# aafilter.net
KiCad netlist of a schematic drawn in Altium Designer
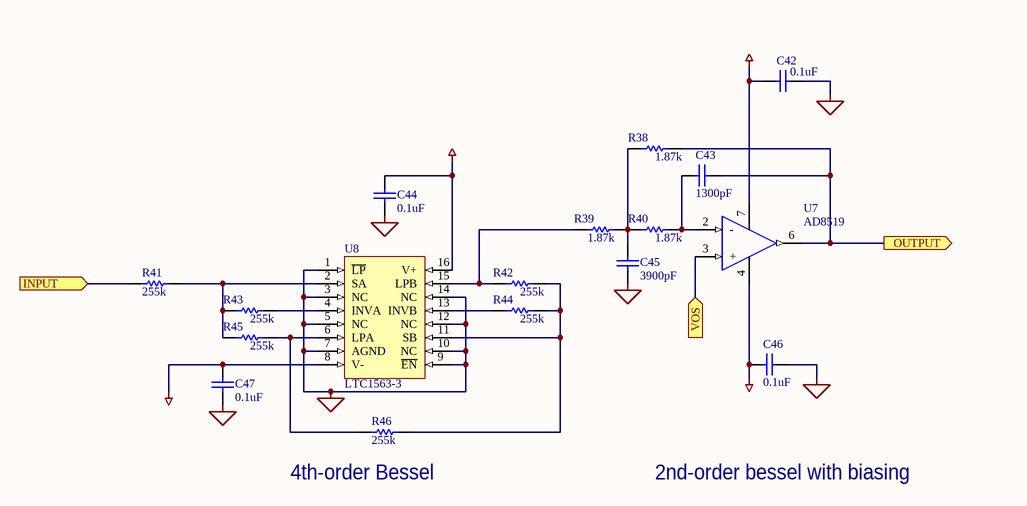
[diagram p0: aafilter.SCHDOC]

(export (version "E")
  (design (tool "Eeschema 10.0.6"))
  (components
    (comp (ref "C42")
      (value "Cap")
      (footprint "CC1608-0603")
      (description "Capacitor")
      (fields
        (field (name "MANUFACTURER") "Generic Components")
        (field (name "ALTIUM_VALUE") "0.1uF")
        (field (name "PUBLISHER") "Altium Limited")
      )
      (libsource (lib "Miscellaneous Devices") (part "Cap"))
    )
    (comp (ref "C43")
      (value "Cap")
      (footprint "CC1608-0603")
      (description "Capacitor")
      (fields
        (field (name "MANUFACTURER") "Generic Components")
        (field (name "ALTIUM_VALUE") "1300pF")
        (field (name "PUBLISHER") "Altium Limited")
      )
      (libsource (lib "Miscellaneous Devices") (part "Cap"))
    )
    (comp (ref "C44")
      (value "Cap")
      (footprint "CC1608-0603")
      (description "Capacitor")
      (fields
        (field (name "MANUFACTURER") "Generic Components")
        (field (name "ALTIUM_VALUE") "0.1uF")
        (field (name "PUBLISHER") "Altium Limited")
      )
      (libsource (lib "Miscellaneous Devices") (part "Cap"))
    )
    (comp (ref "C45")
      (value "Cap")
      (footprint "CC1608-0603")
      (description "Capacitor")
      (fields
        (field (name "MANUFACTURER") "Generic Components")
        (field (name "ALTIUM_VALUE") "3900pF")
        (field (name "PUBLISHER") "Altium Limited")
      )
      (libsource (lib "Miscellaneous Devices") (part "Cap"))
    )
    (comp (ref "C46")
      (value "Cap")
      (footprint "CC1608-0603")
      (description "Capacitor")
      (fields
        (field (name "MANUFACTURER") "Generic Components")
        (field (name "ALTIUM_VALUE") "0.1uF")
        (field (name "PUBLISHER") "Altium Limited")
      )
      (libsource (lib "Miscellaneous Devices") (part "Cap"))
    )
    (comp (ref "C47")
      (value "Cap")
      (footprint "CC1608-0603")
      (description "Capacitor")
      (fields
        (field (name "MANUFACTURER") "Generic Components")
        (field (name "ALTIUM_VALUE") "0.1uF")
        (field (name "PUBLISHER") "Altium Limited")
      )
      (libsource (lib "Miscellaneous Devices") (part "Cap"))
    )
    (comp (ref "R38")
      (value "Res1")
      (footprint "R2012-0805")
      (description "Resistor")
      (fields
        (field (name "MANUFACTURER") "Generic Components")
        (field (name "ALTIUM_VALUE") "1.87k")
        (field (name "PUBLISHER") "Altium Limited")
      )
      (libsource (lib "Miscellaneous Devices") (part "Res1"))
    )
    (comp (ref "R39")
      (value "Res1")
      (footprint "R2012-0805")
      (description "Resistor")
      (fields
        (field (name "MANUFACTURER") "Generic Components")
        (field (name "ALTIUM_VALUE") "1.87k")
        (field (name "PUBLISHER") "Altium Limited")
      )
      (libsource (lib "Miscellaneous Devices") (part "Res1"))
    )
    (comp (ref "R40")
      (value "Res1")
      (footprint "R2012-0805")
      (description "Resistor")
      (fields
        (field (name "MANUFACTURER") "Generic Components")
        (field (name "ALTIUM_VALUE") "1.87k")
        (field (name "PUBLISHER") "Altium Limited")
      )
      (libsource (lib "Miscellaneous Devices") (part "Res1"))
    )
    (comp (ref "R41")
      (value "Res1")
      (footprint "R2012-0805")
      (description "Resistor")
      (fields
        (field (name "MANUFACTURER") "Generic Components")
        (field (name "ALTIUM_VALUE") "255k")
        (field (name "PUBLISHER") "Altium Limited")
      )
      (libsource (lib "Miscellaneous Devices") (part "Res1"))
    )
    (comp (ref "R42")
      (value "Res1")
      (footprint "R2012-0805")
      (description "Resistor")
      (fields
        (field (name "MANUFACTURER") "Generic Components")
        (field (name "ALTIUM_VALUE") "255k")
        (field (name "PUBLISHER") "Altium Limited")
      )
      (libsource (lib "Miscellaneous Devices") (part "Res1"))
    )
    (comp (ref "R43")
      (value "Res1")
      (footprint "R2012-0805")
      (description "Resistor")
      (fields
        (field (name "MANUFACTURER") "Generic Components")
        (field (name "ALTIUM_VALUE") "255k")
        (field (name "PUBLISHER") "Altium Limited")
      )
      (libsource (lib "Miscellaneous Devices") (part "Res1"))
    )
    (comp (ref "R44")
      (value "Res1")
      (footprint "R2012-0805")
      (description "Resistor")
      (fields
        (field (name "MANUFACTURER") "Generic Components")
        (field (name "ALTIUM_VALUE") "255k")
        (field (name "PUBLISHER") "Altium Limited")
      )
      (libsource (lib "Miscellaneous Devices") (part "Res1"))
    )
    (comp (ref "R45")
      (value "Res1")
      (footprint "R2012-0805")
      (description "Resistor")
      (fields
        (field (name "MANUFACTURER") "Generic Components")
        (field (name "ALTIUM_VALUE") "255k")
        (field (name "PUBLISHER") "Altium Limited")
      )
      (libsource (lib "Miscellaneous Devices") (part "Res1"))
    )
    (comp (ref "R46")
      (value "Res1")
      (footprint "R2012-0805")
      (description "Resistor")
      (fields
        (field (name "MANUFACTURER") "Generic Components")
        (field (name "ALTIUM_VALUE") "255k")
        (field (name "PUBLISHER") "Altium Limited")
      )
      (libsource (lib "Miscellaneous Devices") (part "Res1"))
    )
    (comp (ref "U7")
      (value "AD8519")
      (footprint "SO-G8/X.6")
      (description "8 MHz RRIO Op-Amp")
      (libsource (lib "My devices") (part "AD8519"))
    )
    (comp (ref "U8")
      (value "LTC1563-3")
      (footprint "SSO-G16/X.4")
      (description "Linear Tech 4-th order linear continuous filter")
      (libsource (lib "My devices") (part "LTC1563-3"))
    )
  )
  (nets
    (net (code "1") (name "/INPUT") (class "Default")
      (node (ref "R41") (pin "1") (pinfunction "1_1") (pintype "passive"))
    )
    (net (code "2") (name "/OUTPUT") (class "Default")
      (node (ref "C43") (pin "1") (pinfunction "1_1") (pintype "passive"))
      (node (ref "R38") (pin "2") (pinfunction "2_2") (pintype "passive"))
      (node (ref "U7") (pin "6") (pinfunction "Out_6") (pintype "output"))
    )
    (net (code "3") (name "/VOS") (class "Default")
      (node (ref "U7") (pin "3") (pinfunction "+_3") (pintype "input"))
    )
    (net (code "4") (name "AVDD") (class "Default")
      (node (ref "C42") (pin "2") (pinfunction "2_2") (pintype "passive"))
      (node (ref "C44") (pin "2") (pinfunction "2_2") (pintype "passive"))
      (node (ref "U7") (pin "7") (pinfunction "+Vs_7") (pintype "power_in"))
      (node (ref "U8") (pin "16") (pinfunction "V+_16") (pintype "input"))
    )
    (net (code "5") (name "AVSS") (class "Default")
      (node (ref "C46") (pin "2") (pinfunction "2_2") (pintype "passive"))
      (node (ref "C47") (pin "2") (pinfunction "2_2") (pintype "passive"))
      (node (ref "U7") (pin "4") (pinfunction "-Vs_4") (pintype "power_in"))
      (node (ref "U8") (pin "8") (pinfunction "V-_8") (pintype "input"))
    )
    (net (code "6") (name "GND") (class "Default")
      (node (ref "C42") (pin "1") (pinfunction "1_1") (pintype "passive"))
      (node (ref "C44") (pin "1") (pinfunction "1_1") (pintype "passive"))
      (node (ref "C45") (pin "1") (pinfunction "1_1") (pintype "passive"))
      (node (ref "C46") (pin "1") (pinfunction "1_1") (pintype "passive"))
      (node (ref "C47") (pin "1") (pinfunction "1_1") (pintype "passive"))
      (node (ref "U8") (pin "1") (pinfunction "~{LP}_1") (pintype "input"))
      (node (ref "U8") (pin "10") (pinfunction "NC_10") (pintype "input"))
      (node (ref "U8") (pin "12") (pinfunction "NC_12") (pintype "input"))
      (node (ref "U8") (pin "14") (pinfunction "NC_14") (pintype "input"))
      (node (ref "U8") (pin "3") (pinfunction "NC_3") (pintype "input"))
      (node (ref "U8") (pin "5") (pinfunction "NC_5") (pintype "input"))
      (node (ref "U8") (pin "7") (pinfunction "AGND_7") (pintype "input"))
      (node (ref "U8") (pin "9") (pinfunction "~{EN}_9") (pintype "input"))
    )
    (net (code "7") (name "Net-(C45-Pad2)") (class "Default")
      (node (ref "C45") (pin "2") (pinfunction "2_2") (pintype "passive"))
      (node (ref "R38") (pin "1") (pinfunction "1_1") (pintype "passive"))
      (node (ref "R39") (pin "2") (pinfunction "2_2") (pintype "passive"))
      (node (ref "R40") (pin "1") (pinfunction "1_1") (pintype "passive"))
    )
    (net (code "8") (name "Net-(U7--)") (class "Default")
      (node (ref "C43") (pin "2") (pinfunction "2_2") (pintype "passive"))
      (node (ref "R40") (pin "2") (pinfunction "2_2") (pintype "passive"))
      (node (ref "U7") (pin "2") (pinfunction "-_2") (pintype "input"))
    )
    (net (code "9") (name "Net-(U8-INVA)") (class "Default")
      (node (ref "R43") (pin "2") (pinfunction "2_2") (pintype "passive"))
      (node (ref "U8") (pin "4") (pinfunction "INVA_4") (pintype "input"))
    )
    (net (code "10") (name "Net-(U8-INVB)") (class "Default")
      (node (ref "R44") (pin "1") (pinfunction "1_1") (pintype "passive"))
      (node (ref "U8") (pin "13") (pinfunction "INVB_13") (pintype "input"))
    )
    (net (code "11") (name "Net-(U8-LPA)") (class "Default")
      (node (ref "R45") (pin "2") (pinfunction "2_2") (pintype "passive"))
      (node (ref "R46") (pin "1") (pinfunction "1_1") (pintype "passive"))
      (node (ref "U8") (pin "6") (pinfunction "LPA_6") (pintype "input"))
    )
    (net (code "12") (name "Net-(U8-LPB)") (class "Default")
      (node (ref "R39") (pin "1") (pinfunction "1_1") (pintype "passive"))
      (node (ref "R42") (pin "1") (pinfunction "1_1") (pintype "passive"))
      (node (ref "U8") (pin "15") (pinfunction "LPB_15") (pintype "input"))
    )
    (net (code "13") (name "Net-(U8-SA)") (class "Default")
      (node (ref "R41") (pin "2") (pinfunction "2_2") (pintype "passive"))
      (node (ref "R43") (pin "1") (pinfunction "1_1") (pintype "passive"))
      (node (ref "R45") (pin "1") (pinfunction "1_1") (pintype "passive"))
      (node (ref "U8") (pin "2") (pinfunction "SA_2") (pintype "input"))
    )
    (net (code "14") (name "Net-(U8-SB)") (class "Default")
      (node (ref "R42") (pin "2") (pinfunction "2_2") (pintype "passive"))
      (node (ref "R44") (pin "2") (pinfunction "2_2") (pintype "passive"))
      (node (ref "R46") (pin "2") (pinfunction "2_2") (pintype "passive"))
      (node (ref "U8") (pin "11") (pinfunction "SB_11") (pintype "input"))
    )
  )
)
